# PMOD-T3-T6.net
KiCad netlist of a schematic drawn in Altium Designer
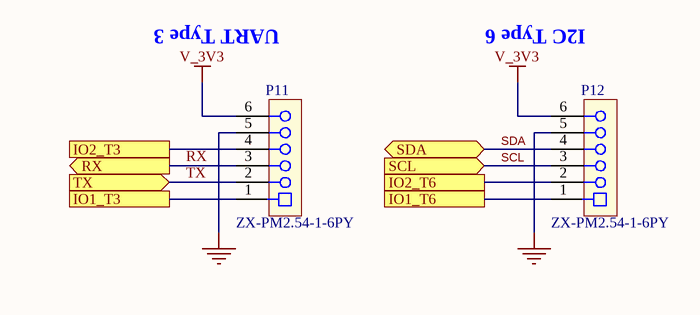
[diagram p0: PMOD-T3-T6.SchDoc]

(export (version "E")
  (design (tool "Eeschema 10.0.6"))
  (components
    (comp (ref "P11")
      (value "ZX-PM2.54-1-6PY")
      (footprint "CONN_SKT_01X06_100MIL")
      (description "CONN SOCKET 6pos 100mils")
      (libsource (lib "TEP_243-AltiumLIB-Conn-TP-MH") (part "CONN-100MIL-SKT-01X06"))
    )
    (comp (ref "P12")
      (value "ZX-PM2.54-1-6PY")
      (footprint "CONN_SKT_01X06_100MIL")
      (description "CONN SOCKET 6pos 100mils")
      (libsource (lib "TEP_243-AltiumLIB-Conn-TP-MH") (part "CONN-100MIL-SKT-01X06"))
    )
  )
  (nets
    (net (code "1") (name "/IO1_T3") (class "Default")
      (node (ref "P11") (pin "1") (pinfunction "1_1") (pintype "passive"))
    )
    (net (code "2") (name "/IO1_T6") (class "Default")
      (node (ref "P12") (pin "1") (pinfunction "1_1") (pintype "passive"))
    )
    (net (code "3") (name "/IO2_T3") (class "Default")
      (node (ref "P11") (pin "4") (pinfunction "4_4") (pintype "passive"))
    )
    (net (code "4") (name "/IO2_T6") (class "Default")
      (node (ref "P12") (pin "2") (pinfunction "2_2") (pintype "passive"))
    )
    (net (code "5") (name "/RX") (class "Default")
      (node (ref "P11") (pin "3") (pinfunction "3_3") (pintype "passive"))
    )
    (net (code "6") (name "/SCL") (class "Default")
      (node (ref "P12") (pin "3") (pinfunction "3_3") (pintype "passive"))
    )
    (net (code "7") (name "/SDA") (class "Default")
      (node (ref "P12") (pin "4") (pinfunction "4_4") (pintype "passive"))
    )
    (net (code "8") (name "/TX") (class "Default")
      (node (ref "P11") (pin "2") (pinfunction "2_2") (pintype "passive"))
    )
    (net (code "9") (name "GND") (class "Default")
      (node (ref "P11") (pin "5") (pinfunction "5_5") (pintype "passive"))
      (node (ref "P12") (pin "5") (pinfunction "5_5") (pintype "passive"))
    )
    (net (code "10") (name "V_3V3") (class "Default")
      (node (ref "P11") (pin "6") (pinfunction "6_6") (pintype "passive"))
      (node (ref "P12") (pin "6") (pinfunction "6_6") (pintype "passive"))
    )
  )
)
